# ProProject_CAM1320_2024-01-19.net
KiCad netlist of a schematic drawn in EasyEDA Pro
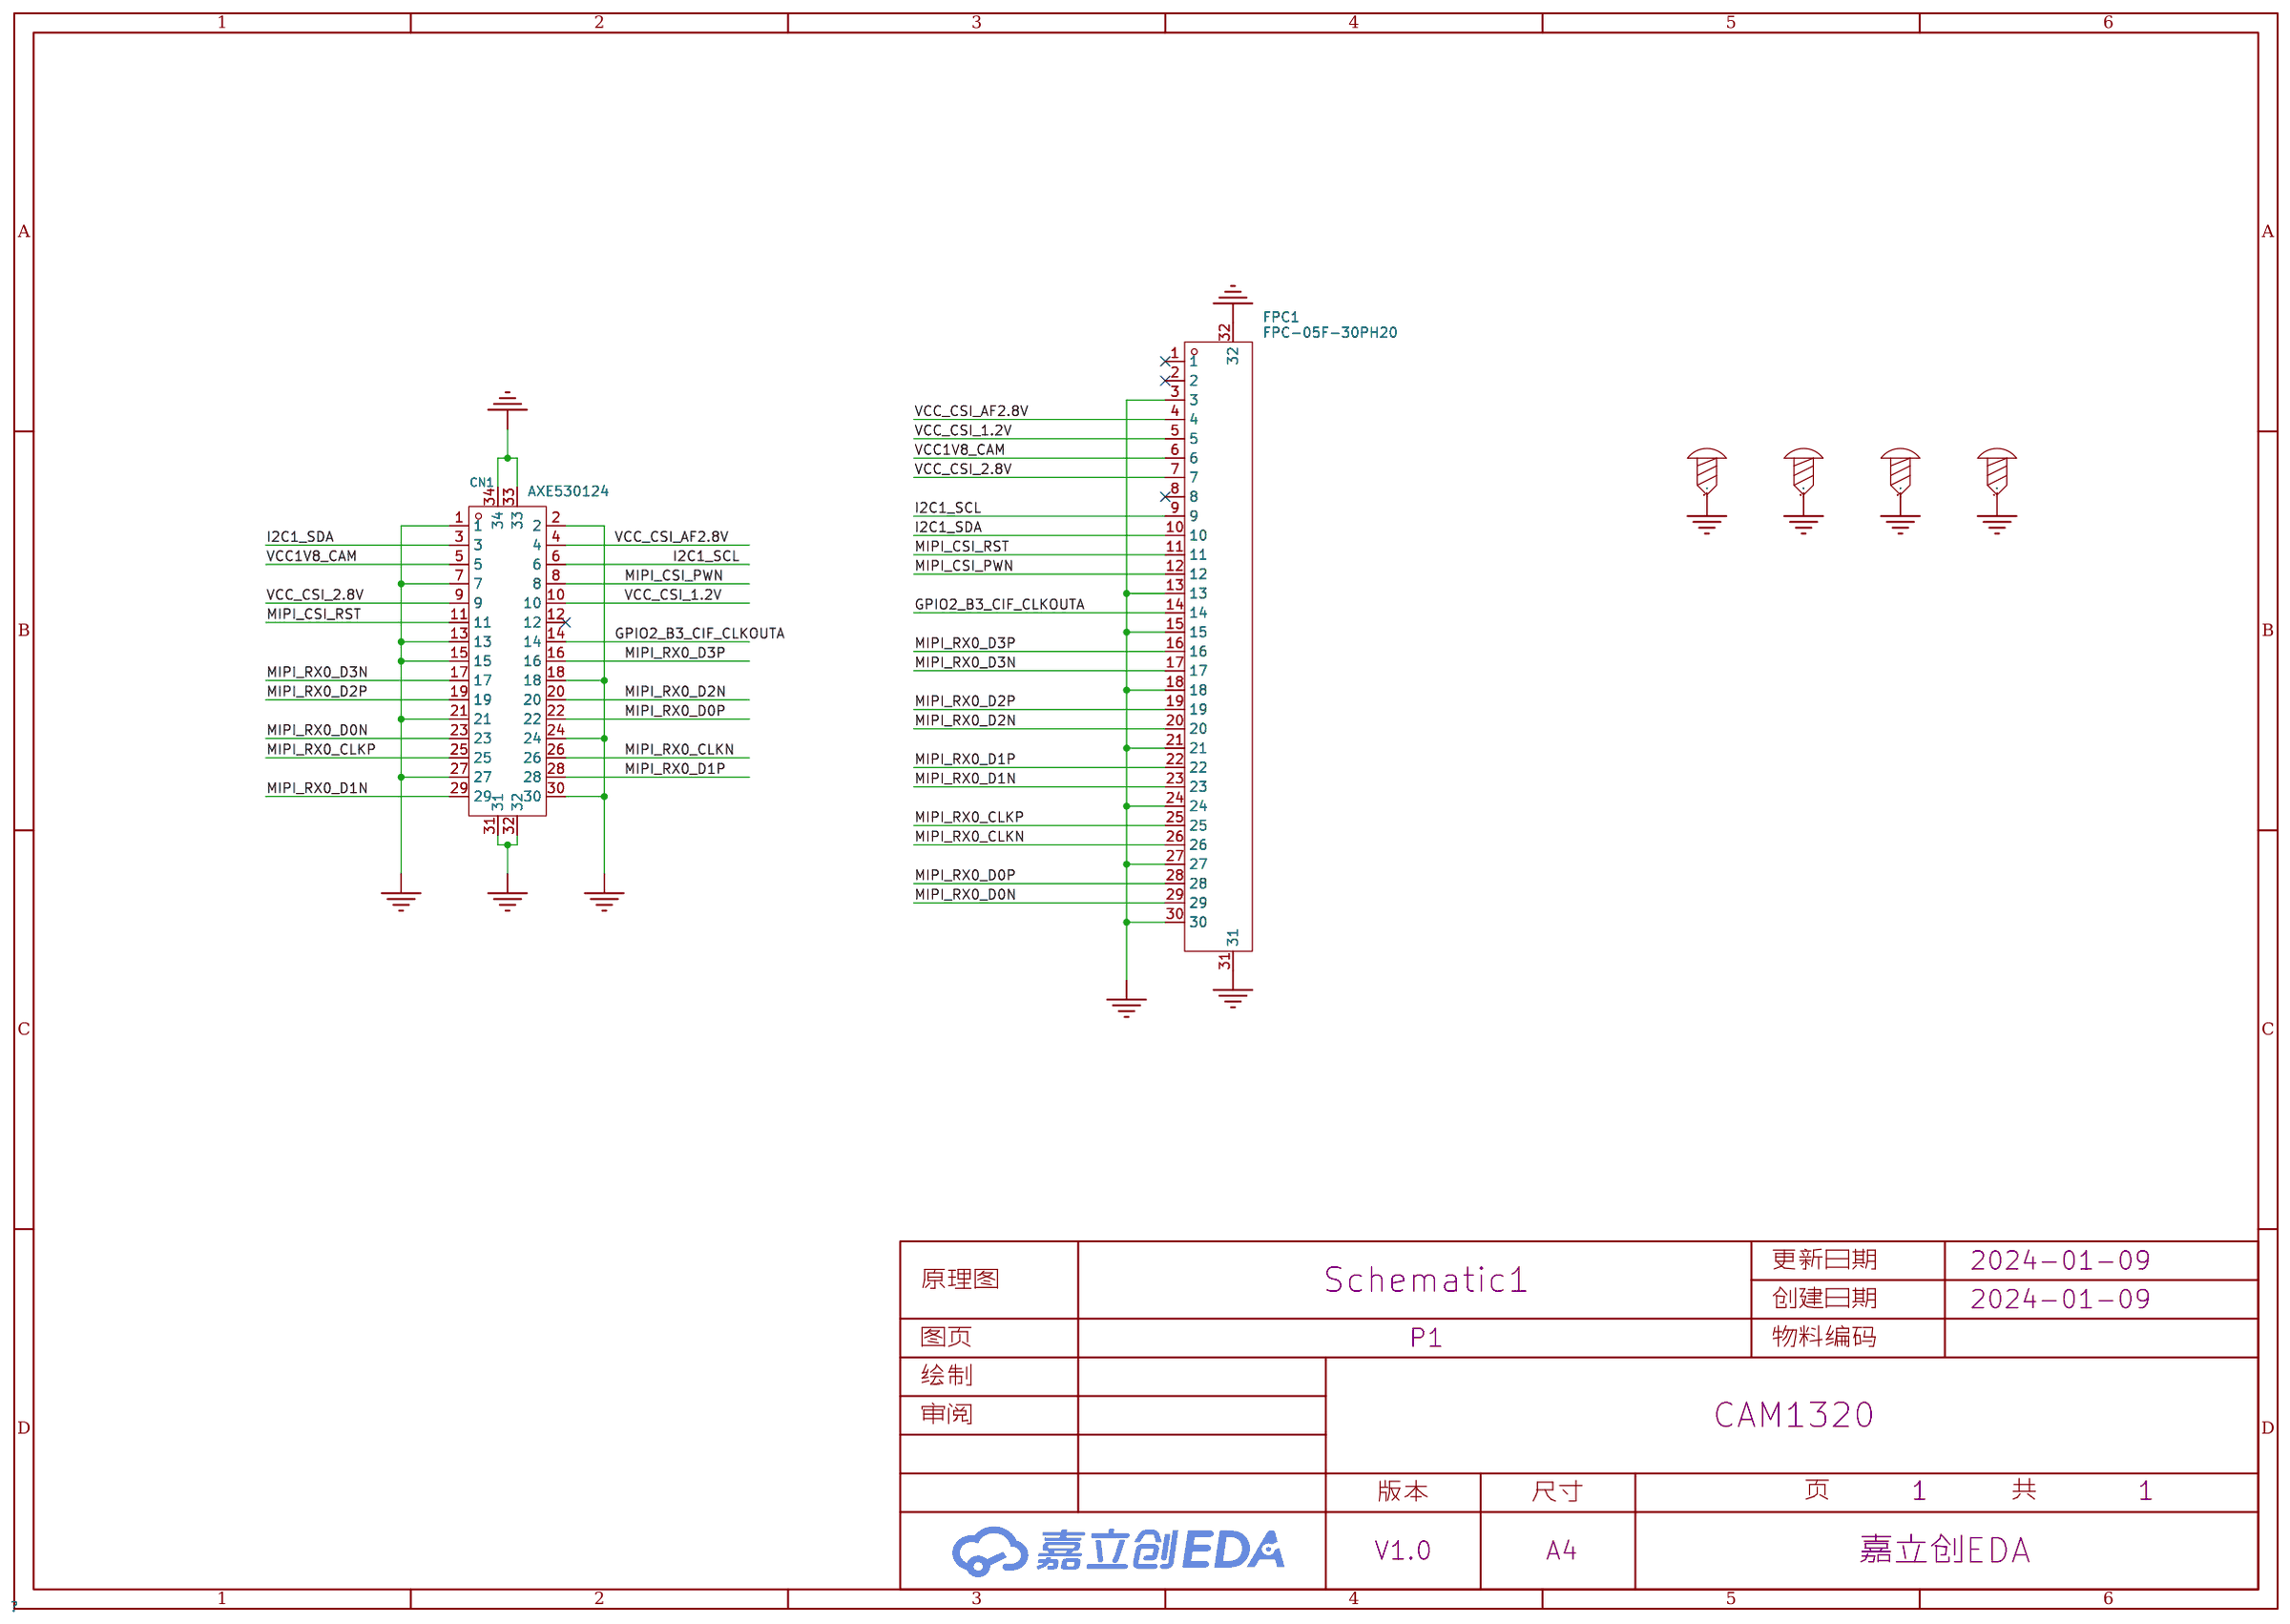
[diagram p0: schematic sheet]

(export (version "E")
  (design (tool "Eeschema 10.0.6"))
  (components
    (comp (ref "CN1")
      (value "AXE530124")
      (footprint "easyedapro:CONN-SMD_30P-P0.40_AXE530124")
      (description "PIN总数:30P;间距:0.4mm;行数:2;公母:母;安装方式:立贴;")
      (fields (field (name "Manufacturer") "PANASONIC(松下)"))
      (libsource (lib "easyedapro") (part "AXE530124"))
    )
    (comp (ref "FPC1")
      (value "FPC-05F-30PH20")
      (footprint "easyedapro:FPC-SMD_30P-P0.50_XUNPU_FPC-05F-30PH20")
      (description "间距:0.5mm;触点数量:30P;锁定特性:翻盖式;触点类型:下接;安装类型:卧贴;工作温度范围:-25°C~+85°C;")
      (fields (field (name "Manufacturer") "XUNPU(讯普)"))
      (libsource (lib "easyedapro") (part "FPC-05F-30PH20"))
    )
    (comp (ref "U1") (value "~") (footprint "easyedapro:M2螺丝") (libsource (lib "easyedapro") (part "螺丝孔")))
    (comp (ref "U2") (value "~") (footprint "easyedapro:M2螺丝") (libsource (lib "easyedapro") (part "螺丝孔")))
    (comp (ref "U3") (value "~") (footprint "easyedapro:M2螺丝") (libsource (lib "easyedapro") (part "螺丝孔")))
    (comp (ref "U4") (value "~") (footprint "easyedapro:M2螺丝") (libsource (lib "easyedapro") (part "螺丝孔")))
  )
  (nets
    (net (code "1") (name "/GPIO2_B3_CIF_CLKOUTA") (class "Default")
      (node (ref "CN1") (pin "14") (pinfunction "14_14") (pintype "input"))
      (node (ref "FPC1") (pin "14") (pinfunction "14_14") (pintype "unspecified"))
    )
    (net (code "2") (name "/I2C1_SCL") (class "Default")
      (node (ref "CN1") (pin "6") (pinfunction "6_6") (pintype "input"))
      (node (ref "FPC1") (pin "9") (pinfunction "9_9") (pintype "unspecified"))
    )
    (net (code "3") (name "/I2C1_SDA") (class "Default")
      (node (ref "CN1") (pin "3") (pinfunction "3_3") (pintype "input"))
      (node (ref "FPC1") (pin "10") (pinfunction "10_10") (pintype "unspecified"))
    )
    (net (code "4") (name "/MIPI_CSI_PWN") (class "Default")
      (node (ref "CN1") (pin "8") (pinfunction "8_8") (pintype "input"))
      (node (ref "FPC1") (pin "12") (pinfunction "12_12") (pintype "unspecified"))
    )
    (net (code "5") (name "/MIPI_CSI_RST") (class "Default")
      (node (ref "CN1") (pin "11") (pinfunction "11_11") (pintype "input"))
      (node (ref "FPC1") (pin "11") (pinfunction "11_11") (pintype "unspecified"))
    )
    (net (code "6") (name "/MIPI_RX0_CLKN") (class "Default")
      (node (ref "CN1") (pin "26") (pinfunction "26_26") (pintype "input"))
      (node (ref "FPC1") (pin "26") (pinfunction "26_26") (pintype "unspecified"))
    )
    (net (code "7") (name "/MIPI_RX0_CLKP") (class "Default")
      (node (ref "CN1") (pin "25") (pinfunction "25_25") (pintype "input"))
      (node (ref "FPC1") (pin "25") (pinfunction "25_25") (pintype "unspecified"))
    )
    (net (code "8") (name "/MIPI_RX0_D0N") (class "Default")
      (node (ref "CN1") (pin "23") (pinfunction "23_23") (pintype "input"))
      (node (ref "FPC1") (pin "29") (pinfunction "29_29") (pintype "unspecified"))
    )
    (net (code "9") (name "/MIPI_RX0_D0P") (class "Default")
      (node (ref "CN1") (pin "22") (pinfunction "22_22") (pintype "input"))
      (node (ref "FPC1") (pin "28") (pinfunction "28_28") (pintype "unspecified"))
    )
    (net (code "10") (name "/MIPI_RX0_D1N") (class "Default")
      (node (ref "CN1") (pin "29") (pinfunction "29_29") (pintype "input"))
      (node (ref "FPC1") (pin "23") (pinfunction "23_23") (pintype "unspecified"))
    )
    (net (code "11") (name "/MIPI_RX0_D1P") (class "Default")
      (node (ref "CN1") (pin "28") (pinfunction "28_28") (pintype "input"))
      (node (ref "FPC1") (pin "22") (pinfunction "22_22") (pintype "unspecified"))
    )
    (net (code "12") (name "/MIPI_RX0_D2N") (class "Default")
      (node (ref "CN1") (pin "20") (pinfunction "20_20") (pintype "input"))
      (node (ref "FPC1") (pin "20") (pinfunction "20_20") (pintype "unspecified"))
    )
    (net (code "13") (name "/MIPI_RX0_D2P") (class "Default")
      (node (ref "CN1") (pin "19") (pinfunction "19_19") (pintype "input"))
      (node (ref "FPC1") (pin "19") (pinfunction "19_19") (pintype "unspecified"))
    )
    (net (code "14") (name "/MIPI_RX0_D3N") (class "Default")
      (node (ref "CN1") (pin "17") (pinfunction "17_17") (pintype "input"))
      (node (ref "FPC1") (pin "17") (pinfunction "17_17") (pintype "unspecified"))
    )
    (net (code "15") (name "/MIPI_RX0_D3P") (class "Default")
      (node (ref "CN1") (pin "16") (pinfunction "16_16") (pintype "input"))
      (node (ref "FPC1") (pin "16") (pinfunction "16_16") (pintype "unspecified"))
    )
    (net (code "16") (name "/VCC1V8_CAM") (class "Default")
      (node (ref "CN1") (pin "5") (pinfunction "5_5") (pintype "input"))
      (node (ref "FPC1") (pin "6") (pinfunction "6_6") (pintype "unspecified"))
    )
    (net (code "17") (name "/VCC_CSI_1.2V") (class "Default")
      (node (ref "CN1") (pin "10") (pinfunction "10_10") (pintype "input"))
      (node (ref "FPC1") (pin "5") (pinfunction "5_5") (pintype "unspecified"))
    )
    (net (code "18") (name "/VCC_CSI_2.8V") (class "Default")
      (node (ref "CN1") (pin "9") (pinfunction "9_9") (pintype "input"))
      (node (ref "FPC1") (pin "7") (pinfunction "7_7") (pintype "unspecified"))
    )
    (net (code "19") (name "/VCC_CSI_AF2.8V") (class "Default")
      (node (ref "CN1") (pin "4") (pinfunction "4_4") (pintype "input"))
      (node (ref "FPC1") (pin "4") (pinfunction "4_4") (pintype "unspecified"))
    )
    (net (code "20") (name "GND") (class "Default")
      (node (ref "CN1") (pin "1") (pinfunction "1_1") (pintype "input"))
      (node (ref "CN1") (pin "13") (pinfunction "13_13") (pintype "input"))
      (node (ref "CN1") (pin "15") (pinfunction "15_15") (pintype "input"))
      (node (ref "CN1") (pin "18") (pinfunction "18_18") (pintype "input"))
      (node (ref "CN1") (pin "2") (pinfunction "2_2") (pintype "input"))
      (node (ref "CN1") (pin "21") (pinfunction "21_21") (pintype "input"))
      (node (ref "CN1") (pin "24") (pinfunction "24_24") (pintype "input"))
      (node (ref "CN1") (pin "27") (pinfunction "27_27") (pintype "input"))
      (node (ref "CN1") (pin "30") (pinfunction "30_30") (pintype "input"))
      (node (ref "CN1") (pin "31") (pinfunction "31_31") (pintype "input"))
      (node (ref "CN1") (pin "32") (pinfunction "32_32") (pintype "input"))
      (node (ref "CN1") (pin "33") (pinfunction "33_33") (pintype "input"))
      (node (ref "CN1") (pin "34") (pinfunction "34_34") (pintype "input"))
      (node (ref "CN1") (pin "7") (pinfunction "7_7") (pintype "input"))
      (node (ref "FPC1") (pin "13") (pinfunction "13_13") (pintype "unspecified"))
      (node (ref "FPC1") (pin "15") (pinfunction "15_15") (pintype "unspecified"))
      (node (ref "FPC1") (pin "18") (pinfunction "18_18") (pintype "unspecified"))
      (node (ref "FPC1") (pin "21") (pinfunction "21_21") (pintype "unspecified"))
      (node (ref "FPC1") (pin "24") (pinfunction "24_24") (pintype "unspecified"))
      (node (ref "FPC1") (pin "27") (pinfunction "27_27") (pintype "unspecified"))
      (node (ref "FPC1") (pin "3") (pinfunction "3_3") (pintype "unspecified"))
      (node (ref "FPC1") (pin "30") (pinfunction "30_30") (pintype "unspecified"))
      (node (ref "FPC1") (pin "31") (pinfunction "31_31") (pintype "unspecified"))
      (node (ref "FPC1") (pin "32") (pinfunction "32_32") (pintype "unspecified"))
      (node (ref "U1") (pin "1") (pinfunction "1_1") (pintype "input"))
      (node (ref "U2") (pin "1") (pinfunction "1_1") (pintype "input"))
      (node (ref "U3") (pin "1") (pinfunction "1_1") (pintype "input"))
      (node (ref "U4") (pin "1") (pinfunction "1_1") (pintype "input"))
    )
    (net (code "21") (name "unconnected-(CN1-Pad12)") (class "Default")
      (node (ref "CN1") (pin "12") (pinfunction "12_12") (pintype "input+no_connect"))
    )
    (net (code "22") (name "unconnected-(FPC1-Pad1)") (class "Default")
      (node (ref "FPC1") (pin "1") (pinfunction "1_1") (pintype "unspecified+no_connect"))
    )
    (net (code "23") (name "unconnected-(FPC1-Pad2)") (class "Default")
      (node (ref "FPC1") (pin "2") (pinfunction "2_2") (pintype "unspecified+no_connect"))
    )
    (net (code "24") (name "unconnected-(FPC1-Pad8)") (class "Default")
      (node (ref "FPC1") (pin "8") (pinfunction "8_8") (pintype "unspecified+no_connect"))
    )
  )
)
